# Basic_LiPo_Charger.net
KiCad netlist of a schematic drawn in EAGLE
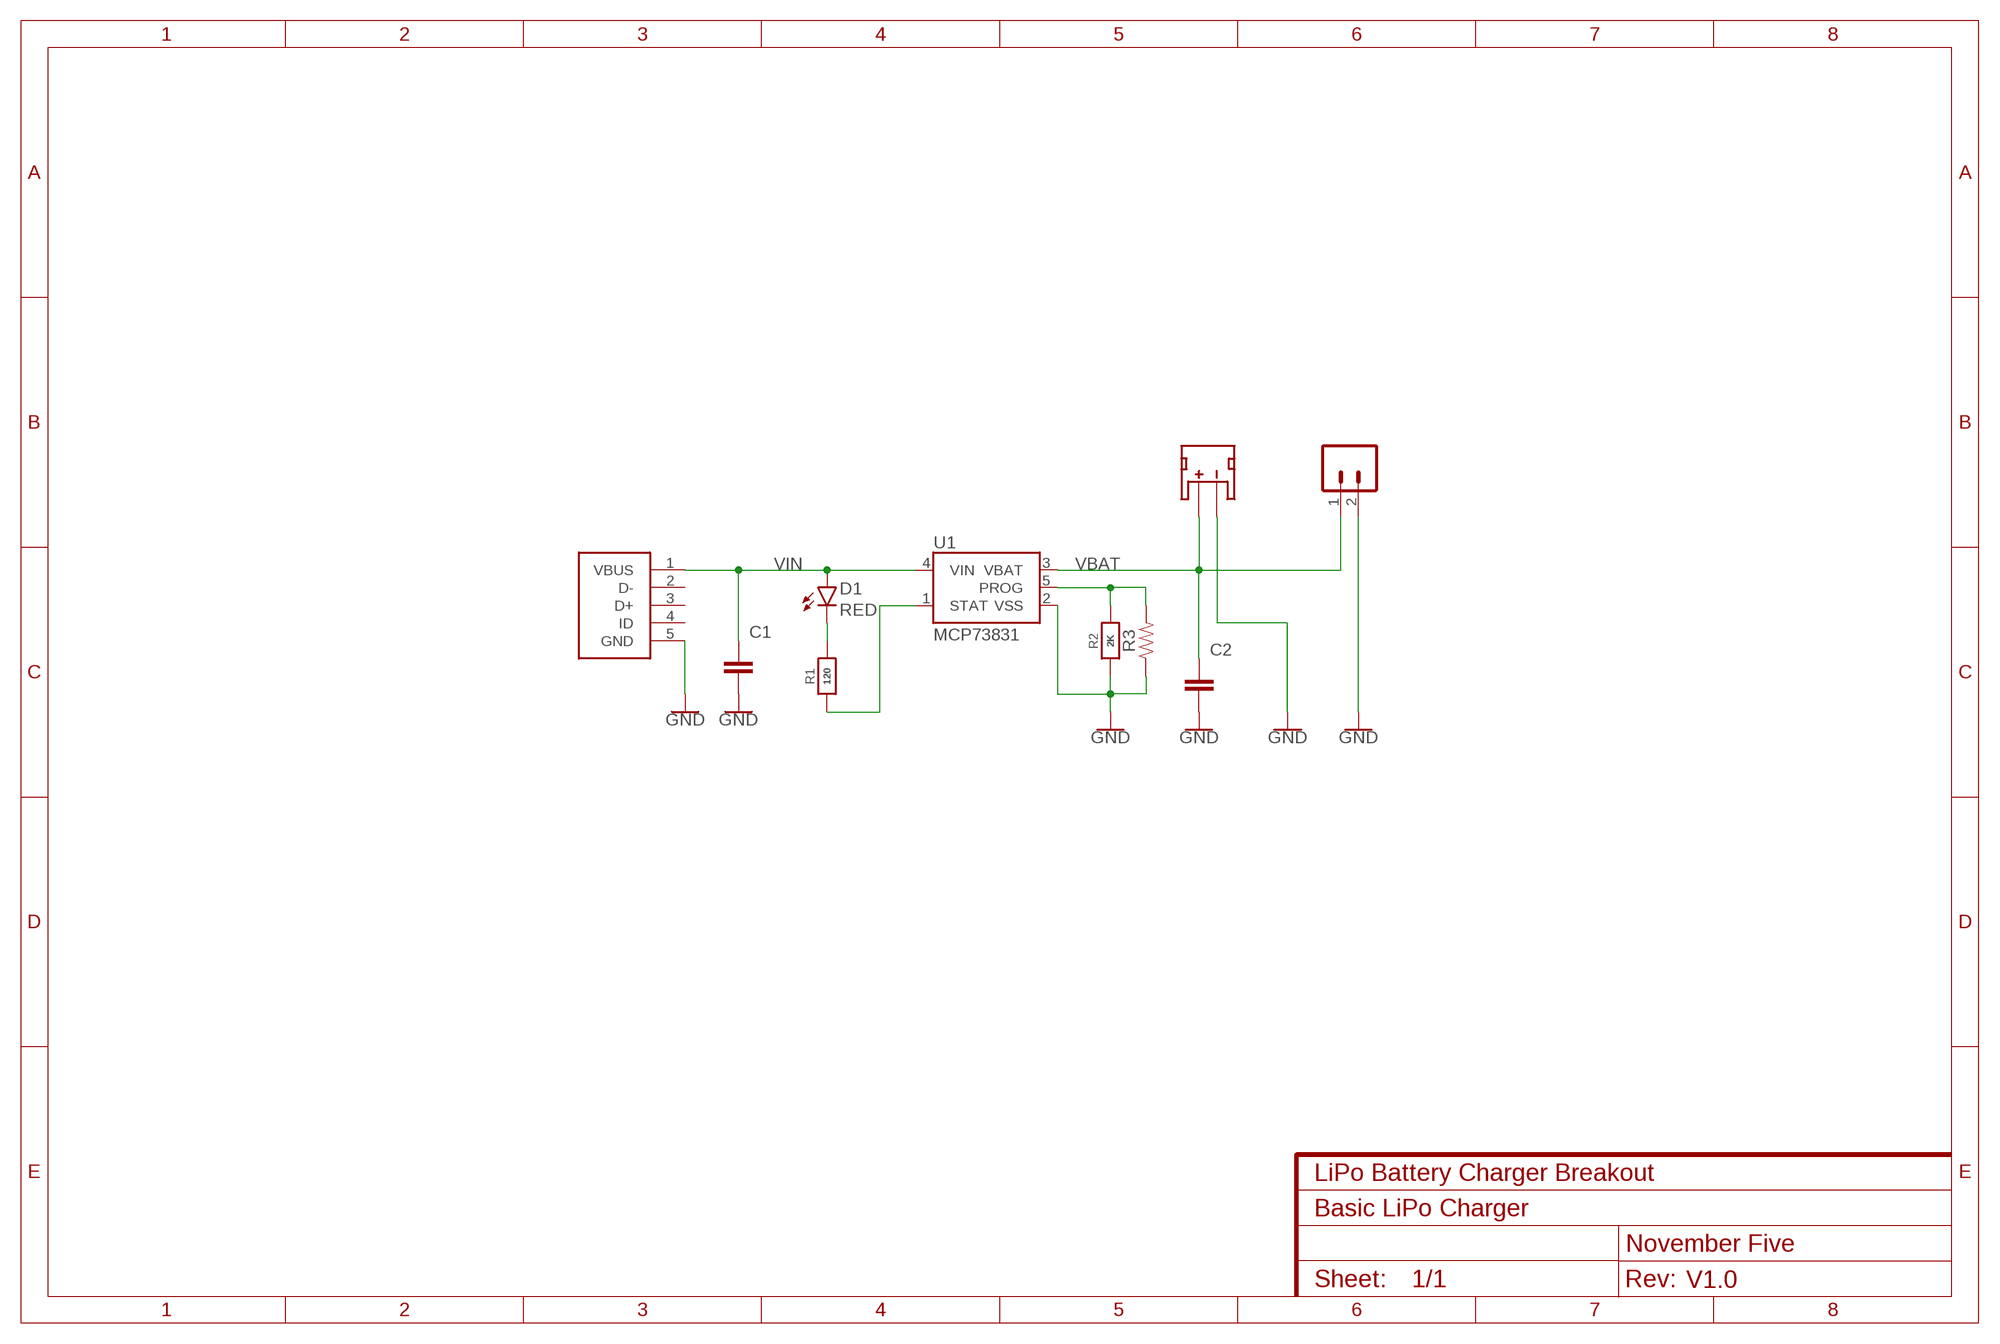
[diagram p0: schematic, sheet 1]

(export (version "E")
  (design (tool "Eeschema 10.0.6"))
  (components
    (comp (ref "C1")
      (value "4.7uF")
      (footprint "eagle-import:C0603")
      (libsource (lib "eagle-import") (part "CAPACITOR"))
    )
    (comp (ref "C2")
      (value "4.7uF")
      (footprint "eagle-import:C0603")
      (libsource (lib "eagle-import") (part "CAPACITOR"))
    )
    (comp (ref "D1")
      (value "RED")
      (footprint "eagle-import:LED-0603")
      (libsource (lib "eagle-import") (part "LED-RED0603"))
    )
    (comp (ref "J1")
      (value "USB-CON-5PIN-105017-0001")
      (footprint "eagle-import:USB-MICRO-MOLEX-105017-0001")
      (libsource (lib "eagle-import") (part "USB-CON-5PIN-105017-0001"))
    )
    (comp (ref "J2")
      (value "JST_2MM_MALE")
      (footprint "eagle-import:JST-2-SMD")
      (libsource (lib "eagle-import") (part "JST_2MM_MALE"))
    )
    (comp (ref "J3")
      (value "CONN_02")
      (footprint "eagle-import:1X02")
      (libsource (lib "eagle-import") (part "CONN_02"))
    )
    (comp (ref "R1")
      (value "120")
      (footprint "eagle-import:R0603")
      (libsource (lib "eagle-import") (part "RESISTOR"))
    )
    (comp (ref "R2")
      (value "2K")
      (footprint "eagle-import:R0603")
      (libsource (lib "eagle-import") (part "RESISTOR"))
    )
    (comp (ref "R3")
      (value "10MOHM-HORIZ-1/4W-5%")
      (footprint "eagle-import:AXIAL-0.3")
      (libsource (lib "eagle-import") (part "10MOHM-HORIZ-1/4W-5%"))
    )
    (comp (ref "U1")
      (value "MCP73831")
      (footprint "eagle-import:SOT23-5")
      (libsource (lib "eagle-import") (part "MCP73831"))
    )
  )
  (nets
    (net (code "1") (name "/VBAT") (class "Default")
      (node (ref "C2") (pin "1") (pinfunction "1_1") (pintype "passive"))
      (node (ref "J2") (pin "2") (pinfunction "+_2") (pintype "bidirectional"))
      (node (ref "J3") (pin "1") (pinfunction "1_1") (pintype "passive"))
      (node (ref "U1") (pin "3") (pinfunction "VBAT_3") (pintype "power_in"))
    )
    (net (code "2") (name "/VIN") (class "Default")
      (node (ref "C1") (pin "1") (pinfunction "1_1") (pintype "passive"))
      (node (ref "D1") (pin "A") (pinfunction "A_A") (pintype "passive"))
      (node (ref "J1") (pin "1") (pinfunction "VBUS_1") (pintype "power_in"))
      (node (ref "U1") (pin "4") (pinfunction "VIN_4") (pintype "power_in"))
    )
    (net (code "3") (name "GND") (class "Default")
      (node (ref "C1") (pin "2") (pinfunction "2_2") (pintype "passive"))
      (node (ref "C2") (pin "2") (pinfunction "2_2") (pintype "passive"))
      (node (ref "J1") (pin "5") (pinfunction "GND_5") (pintype "power_in"))
      (node (ref "J2") (pin "1") (pinfunction "-_1") (pintype "bidirectional"))
      (node (ref "J3") (pin "2") (pinfunction "2_2") (pintype "passive"))
      (node (ref "R2") (pin "1") (pinfunction "1_1") (pintype "passive"))
      (node (ref "R3") (pin "P$1") (pinfunction "1_P$1") (pintype "passive"))
      (node (ref "U1") (pin "2") (pinfunction "VSS_2") (pintype "power_in"))
    )
    (net (code "4") (name "Net-(D1-PadC)") (class "Default")
      (node (ref "D1") (pin "C") (pinfunction "C_C") (pintype "passive"))
      (node (ref "R1") (pin "2") (pinfunction "2_2") (pintype "passive"))
    )
    (net (code "5") (name "Net-(R3-2)") (class "Default")
      (node (ref "R2") (pin "2") (pinfunction "2_2") (pintype "passive"))
      (node (ref "R3") (pin "P$2") (pinfunction "2_P$2") (pintype "passive"))
      (node (ref "U1") (pin "5") (pinfunction "PROG_5") (pintype "input"))
    )
    (net (code "6") (name "Net-(U1-STAT)") (class "Default")
      (node (ref "R1") (pin "1") (pinfunction "1_1") (pintype "passive"))
      (node (ref "U1") (pin "1") (pinfunction "STAT_1") (pintype "output"))
    )
    (net (code "7") (name "unconnected-(J1-D+-Pad3)") (class "Default")
      (node (ref "J1") (pin "3") (pinfunction "D+_3") (pintype "bidirectional"))
    )
    (net (code "8") (name "unconnected-(J1-D--Pad2)") (class "Default")
      (node (ref "J1") (pin "2") (pinfunction "D-_2") (pintype "bidirectional"))
    )
    (net (code "9") (name "unconnected-(J1-ID-Pad4)") (class "Default")
      (node (ref "J1") (pin "4") (pinfunction "ID_4") (pintype "bidirectional"))
    )
    (net (code "10") (name "unconnected-(J2-PAD1-PadNC1)") (class "Default")
      (node (ref "J2") (pin "NC1") (pinfunction "PAD1_NC1") (pintype "bidirectional"))
    )
    (net (code "11") (name "unconnected-(J2-PAD2-PadNC2)") (class "Default")
      (node (ref "J2") (pin "NC2") (pinfunction "PAD2_NC2") (pintype "bidirectional"))
    )
  )
)
